# AcceLog_v00.net
KiCad netlist of a schematic drawn in EAGLE
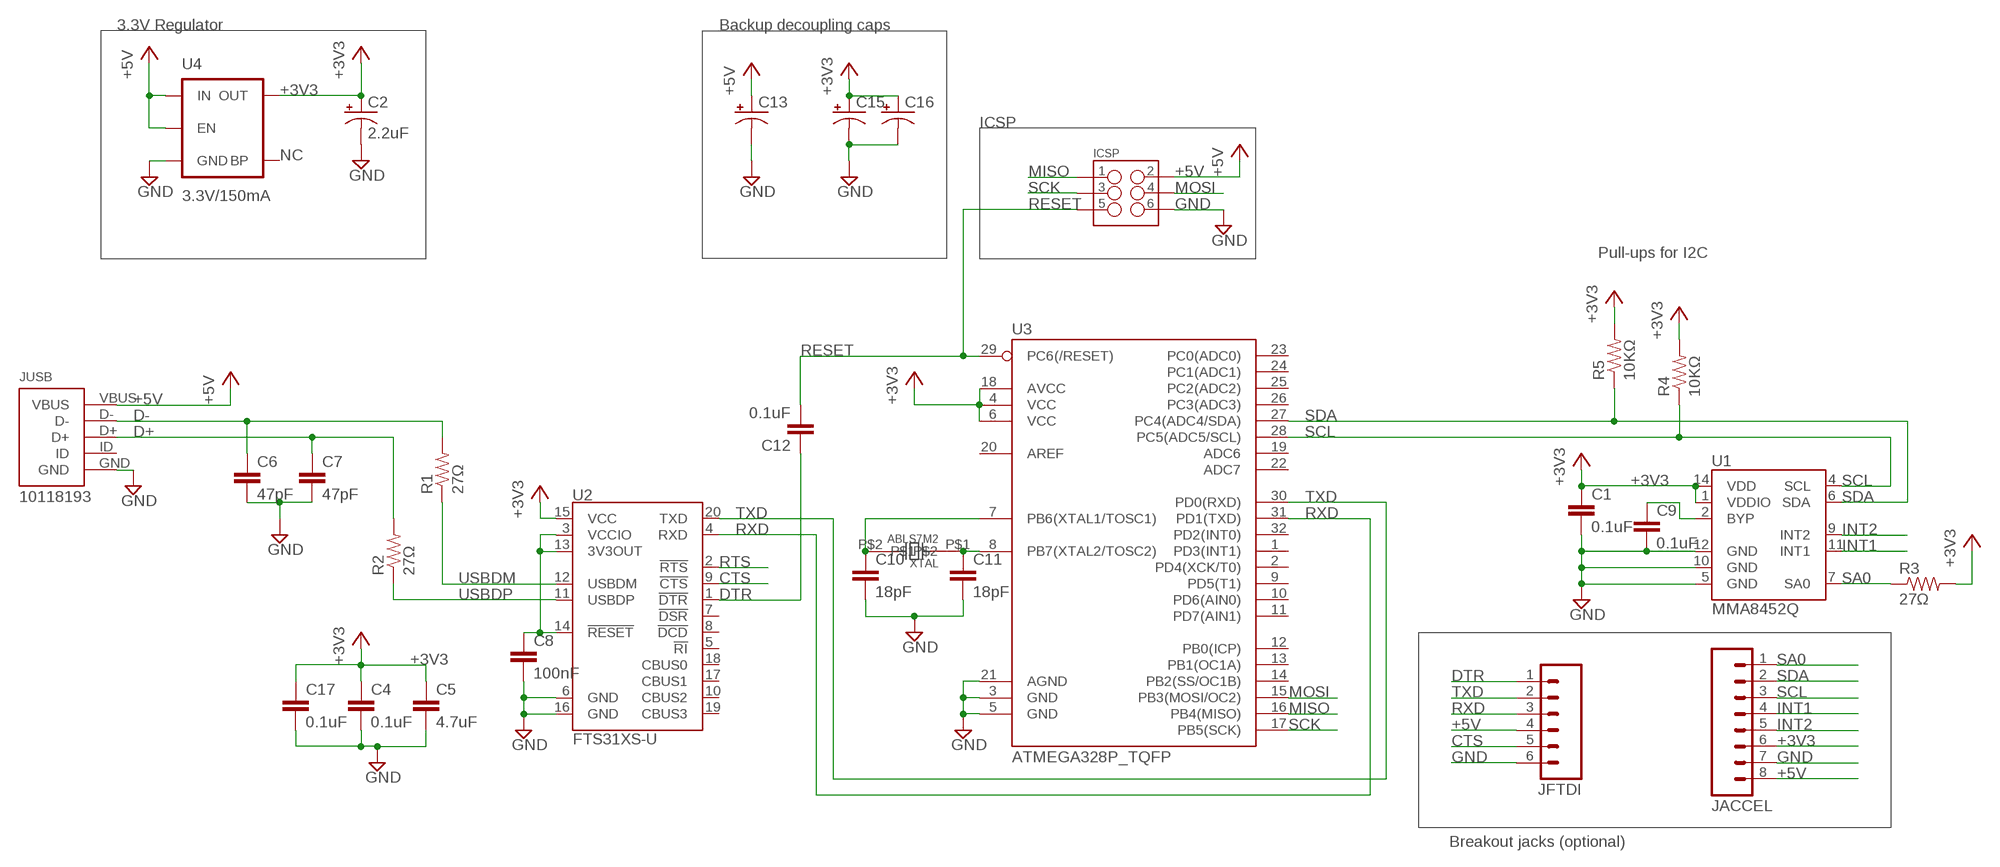
[diagram p0: schematic, sheet 1]

(export (version "E")
  (design (tool "Eeschema 10.0.6"))
  (components
    (comp (ref "C1")
      (value "0.1uF")
      (footprint "eagle-import:0603-CAP")
      (libsource (lib "eagle-import") (part "CAP0603-CAP"))
    )
    (comp (ref "C2")
      (value "2.2uF")
      (footprint "eagle-import:EIA3216")
      (libsource (lib "eagle-import") (part "CAP_POL1206"))
    )
    (comp (ref "C4")
      (value "0.1uF")
      (footprint "eagle-import:0603-CAP")
      (libsource (lib "eagle-import") (part "CAP0603-CAP"))
    )
    (comp (ref "C5")
      (value "4.7uF")
      (footprint "eagle-import:0603-CAP")
      (libsource (lib "eagle-import") (part "CAP0603-CAP"))
    )
    (comp (ref "C6")
      (value "47pF")
      (footprint "eagle-import:0603-CAP")
      (libsource (lib "eagle-import") (part "CAP0603-CAP"))
    )
    (comp (ref "C7")
      (value "47pF")
      (footprint "eagle-import:0603-CAP")
      (libsource (lib "eagle-import") (part "CAP0603-CAP"))
    )
    (comp (ref "C8")
      (value "100nF")
      (footprint "eagle-import:0603-CAP")
      (libsource (lib "eagle-import") (part "CAP0603-CAP"))
    )
    (comp (ref "C9")
      (value "0.1uF")
      (footprint "eagle-import:0603-CAP")
      (libsource (lib "eagle-import") (part "CAP0603-CAP"))
    )
    (comp (ref "C10")
      (value "18pF")
      (footprint "eagle-import:0603-CAP")
      (libsource (lib "eagle-import") (part "CAP0603-CAP"))
    )
    (comp (ref "C11")
      (value "18pF")
      (footprint "eagle-import:0603-CAP")
      (libsource (lib "eagle-import") (part "CAP0603-CAP"))
    )
    (comp (ref "C12")
      (value "0.1uF")
      (footprint "eagle-import:0603-CAP")
      (libsource (lib "eagle-import") (part "CAP0603-CAP"))
    )
    (comp (ref "C13")
      (value "CPOL-USE2-5")
      (footprint "eagle-import:E2-5")
      (libsource (lib "eagle-import") (part "CPOL-USE2-5"))
    )
    (comp (ref "C15")
      (value "CPOL-USE2-5")
      (footprint "eagle-import:E2-5")
      (libsource (lib "eagle-import") (part "CPOL-USE2-5"))
    )
    (comp (ref "C16")
      (value "CPOL-USE2-5")
      (footprint "eagle-import:E2-5")
      (libsource (lib "eagle-import") (part "CPOL-USE2-5"))
    )
    (comp (ref "C17")
      (value "0.1uF")
      (footprint "eagle-import:0603-CAP")
      (libsource (lib "eagle-import") (part "CAP0603-CAP"))
    )
    (comp (ref "ICSP")
      (value "M03X22X3_SILK_MALE_PTH")
      (footprint "eagle-import:2X3")
      (libsource (lib "eagle-import") (part "M03X22X3_SILK_MALE_PTH"))
    )
    (comp (ref "JACCEL")
      (value "M08LOCK")
      (footprint "eagle-import:1X08_LOCK")
      (libsource (lib "eagle-import") (part "M08LOCK"))
    )
    (comp (ref "JFTDI")
      (value "M06LOCK")
      (footprint "eagle-import:1X06_LOCK")
      (libsource (lib "eagle-import") (part "M06LOCK"))
    )
    (comp (ref "JUSB")
      (value "10118193")
      (footprint "eagle-import:10118193")
      (libsource (lib "eagle-import") (part "10118193"))
    )
    (comp (ref "R1")
      (value "27Ω")
      (footprint "eagle-import:0603-RES")
      (libsource (lib "eagle-import") (part "RESISTOR0603-RES"))
    )
    (comp (ref "R2")
      (value "27Ω")
      (footprint "eagle-import:0603-RES")
      (libsource (lib "eagle-import") (part "RESISTOR0603-RES"))
    )
    (comp (ref "R3")
      (value "27Ω")
      (footprint "eagle-import:0603-RES")
      (libsource (lib "eagle-import") (part "RESISTOR0603-RES"))
    )
    (comp (ref "R4")
      (value "10KΩ")
      (footprint "eagle-import:0603-RES")
      (libsource (lib "eagle-import") (part "RESISTOR0603-RES"))
    )
    (comp (ref "R5")
      (value "10KΩ")
      (footprint "eagle-import:0603-RES")
      (libsource (lib "eagle-import") (part "RESISTOR0603-RES"))
    )
    (comp (ref "U1")
      (value "MMA8452Q")
      (footprint "eagle-import:QFN-16_0.5MM")
      (libsource (lib "eagle-import") (part "MMA8452Q"))
    )
    (comp (ref "U2")
      (value "FTS31XS-U")
      (footprint "eagle-import:SSOP20_L")
      (libsource (lib "eagle-import") (part "FT231XS"))
    )
    (comp (ref "U3")
      (value "ATMEGA328P_TQFP")
      (footprint "eagle-import:TQFP32-08")
      (libsource (lib "eagle-import") (part "ATMEGA328P_TQFP"))
    )
    (comp (ref "U4")
      (value "3.3V/150mA")
      (footprint "eagle-import:SOT23-5")
      (libsource (lib "eagle-import") (part "V_REG_MIC52053.3V"))
    )
    (comp (ref "XTAL")
      (value "ABLS7M2")
      (footprint "eagle-import:ABLS7M2")
      (libsource (lib "eagle-import") (part "ABLS7M2"))
    )
  )
  (nets
    (net (code "1") (name "+3V3") (class "Default")
      (node (ref "C1") (pin "1") (pinfunction "1_1") (pintype "passive"))
      (node (ref "C15") (pin "+") (pinfunction "+_+") (pintype "passive"))
      (node (ref "C16") (pin "+") (pinfunction "+_+") (pintype "passive"))
      (node (ref "C17") (pin "1") (pinfunction "1_1") (pintype "passive"))
      (node (ref "C2") (pin "A") (pinfunction "+_A") (pintype "passive"))
      (node (ref "C4") (pin "1") (pinfunction "1_1") (pintype "passive"))
      (node (ref "C5") (pin "1") (pinfunction "1_1") (pintype "passive"))
      (node (ref "JACCEL") (pin "6") (pinfunction "6_6") (pintype "passive"))
      (node (ref "R3") (pin "2") (pinfunction "2_2") (pintype "passive"))
      (node (ref "R4") (pin "2") (pinfunction "2_2") (pintype "passive"))
      (node (ref "R5") (pin "2") (pinfunction "2_2") (pintype "passive"))
      (node (ref "U1") (pin "1") (pinfunction "VDDIO_1") (pintype "bidirectional"))
      (node (ref "U1") (pin "14") (pinfunction "VDD_14") (pintype "bidirectional"))
      (node (ref "U2") (pin "15") (pinfunction "VCC_15") (pintype "bidirectional"))
      (node (ref "U3") (pin "18") (pinfunction "AVCC_18") (pintype "bidirectional"))
      (node (ref "U3") (pin "4") (pinfunction "VCC_4") (pintype "bidirectional"))
      (node (ref "U3") (pin "6") (pinfunction "VCC_6") (pintype "bidirectional"))
      (node (ref "U4") (pin "5") (pinfunction "OUT_5") (pintype "passive"))
    )
    (net (code "2") (name "+5V") (class "Default")
      (node (ref "C13") (pin "+") (pinfunction "+_+") (pintype "passive"))
      (node (ref "ICSP") (pin "2") (pinfunction "2_2") (pintype "bidirectional"))
      (node (ref "JACCEL") (pin "8") (pinfunction "8_8") (pintype "passive"))
      (node (ref "JFTDI") (pin "4") (pinfunction "4_4") (pintype "passive"))
      (node (ref "JUSB") (pin "VBUS") (pinfunction "VBUS_VBUS") (pintype "bidirectional"))
      (node (ref "U4") (pin "1") (pinfunction "IN_1") (pintype "input"))
      (node (ref "U4") (pin "3") (pinfunction "EN_3") (pintype "input"))
    )
    (net (code "3") (name "/CTS") (class "Default")
      (node (ref "JFTDI") (pin "5") (pinfunction "5_5") (pintype "passive"))
      (node (ref "U2") (pin "9") (pinfunction "~{CTS}_9") (pintype "bidirectional"))
    )
    (net (code "4") (name "/D+") (class "Default")
      (node (ref "C7") (pin "1") (pinfunction "1_1") (pintype "passive"))
      (node (ref "JUSB") (pin "D+") (pinfunction "D+_D+") (pintype "bidirectional"))
      (node (ref "R2") (pin "2") (pinfunction "2_2") (pintype "passive"))
    )
    (net (code "5") (name "/D-") (class "Default")
      (node (ref "C6") (pin "1") (pinfunction "1_1") (pintype "passive"))
      (node (ref "JUSB") (pin "D-") (pinfunction "D-_D-") (pintype "bidirectional"))
      (node (ref "R1") (pin "2") (pinfunction "2_2") (pintype "passive"))
    )
    (net (code "6") (name "/DTR") (class "Default")
      (node (ref "C12") (pin "1") (pinfunction "1_1") (pintype "passive"))
      (node (ref "JFTDI") (pin "1") (pinfunction "1_1") (pintype "passive"))
      (node (ref "U2") (pin "1") (pinfunction "~{DTR}_1") (pintype "bidirectional"))
    )
    (net (code "7") (name "/INT1") (class "Default")
      (node (ref "JACCEL") (pin "4") (pinfunction "4_4") (pintype "passive"))
      (node (ref "U1") (pin "11") (pinfunction "INT1_11") (pintype "bidirectional"))
    )
    (net (code "8") (name "/INT2") (class "Default")
      (node (ref "JACCEL") (pin "5") (pinfunction "5_5") (pintype "passive"))
      (node (ref "U1") (pin "9") (pinfunction "INT2_9") (pintype "bidirectional"))
    )
    (net (code "9") (name "/MISO") (class "Default")
      (node (ref "ICSP") (pin "1") (pinfunction "1_1") (pintype "bidirectional"))
      (node (ref "U3") (pin "16") (pinfunction "PB4(MISO)_16") (pintype "bidirectional"))
    )
    (net (code "10") (name "/MOSI") (class "Default")
      (node (ref "ICSP") (pin "4") (pinfunction "4_4") (pintype "bidirectional"))
      (node (ref "U3") (pin "15") (pinfunction "PB3(MOSI/OC2)_15") (pintype "bidirectional"))
    )
    (net (code "11") (name "/RESET") (class "Default")
      (node (ref "C12") (pin "2") (pinfunction "2_2") (pintype "passive"))
      (node (ref "ICSP") (pin "5") (pinfunction "5_5") (pintype "bidirectional"))
      (node (ref "U3") (pin "29") (pinfunction "PC6(/RESET)_29") (pintype "bidirectional"))
    )
    (net (code "12") (name "/RTS") (class "Default")
      (node (ref "U2") (pin "2") (pinfunction "~{RTS}_2") (pintype "bidirectional"))
    )
    (net (code "13") (name "/RXD") (class "Default")
      (node (ref "JFTDI") (pin "3") (pinfunction "3_3") (pintype "passive"))
      (node (ref "U2") (pin "4") (pinfunction "RXD_4") (pintype "bidirectional"))
      (node (ref "U3") (pin "31") (pinfunction "PD1(TXD)_31") (pintype "bidirectional"))
    )
    (net (code "14") (name "/SA0") (class "Default")
      (node (ref "JACCEL") (pin "1") (pinfunction "1_1") (pintype "passive"))
      (node (ref "R3") (pin "1") (pinfunction "1_1") (pintype "passive"))
      (node (ref "U1") (pin "7") (pinfunction "SA0_7") (pintype "bidirectional"))
    )
    (net (code "15") (name "/SCK") (class "Default")
      (node (ref "ICSP") (pin "3") (pinfunction "3_3") (pintype "bidirectional"))
      (node (ref "U3") (pin "17") (pinfunction "PB5(SCK)_17") (pintype "bidirectional"))
    )
    (net (code "16") (name "/SCL") (class "Default")
      (node (ref "JACCEL") (pin "3") (pinfunction "3_3") (pintype "passive"))
      (node (ref "R4") (pin "1") (pinfunction "1_1") (pintype "passive"))
      (node (ref "U1") (pin "4") (pinfunction "SCL_4") (pintype "bidirectional"))
      (node (ref "U3") (pin "28") (pinfunction "PC5(ADC5/SCL)_28") (pintype "bidirectional"))
    )
    (net (code "17") (name "/SDA") (class "Default")
      (node (ref "JACCEL") (pin "2") (pinfunction "2_2") (pintype "passive"))
      (node (ref "R5") (pin "1") (pinfunction "1_1") (pintype "passive"))
      (node (ref "U1") (pin "6") (pinfunction "SDA_6") (pintype "bidirectional"))
      (node (ref "U3") (pin "27") (pinfunction "PC4(ADC4/SDA)_27") (pintype "bidirectional"))
    )
    (net (code "18") (name "/TXD") (class "Default")
      (node (ref "JFTDI") (pin "2") (pinfunction "2_2") (pintype "passive"))
      (node (ref "U2") (pin "20") (pinfunction "TXD_20") (pintype "bidirectional"))
      (node (ref "U3") (pin "30") (pinfunction "PD0(RXD)_30") (pintype "bidirectional"))
    )
    (net (code "19") (name "/USBDM") (class "Default")
      (node (ref "R1") (pin "1") (pinfunction "1_1") (pintype "passive"))
      (node (ref "U2") (pin "12") (pinfunction "USBDM_12") (pintype "bidirectional"))
    )
    (net (code "20") (name "/USBDP") (class "Default")
      (node (ref "R2") (pin "1") (pinfunction "1_1") (pintype "passive"))
      (node (ref "U2") (pin "11") (pinfunction "USBDP_11") (pintype "bidirectional"))
    )
    (net (code "21") (name "GND") (class "Default")
      (node (ref "C1") (pin "2") (pinfunction "2_2") (pintype "passive"))
      (node (ref "C10") (pin "2") (pinfunction "2_2") (pintype "passive"))
      (node (ref "C11") (pin "2") (pinfunction "2_2") (pintype "passive"))
      (node (ref "C13") (pin "-") (pinfunction "-_-") (pintype "passive"))
      (node (ref "C15") (pin "-") (pinfunction "-_-") (pintype "passive"))
      (node (ref "C16") (pin "-") (pinfunction "-_-") (pintype "passive"))
      (node (ref "C17") (pin "2") (pinfunction "2_2") (pintype "passive"))
      (node (ref "C2") (pin "C") (pinfunction "-_C") (pintype "passive"))
      (node (ref "C4") (pin "2") (pinfunction "2_2") (pintype "passive"))
      (node (ref "C5") (pin "2") (pinfunction "2_2") (pintype "passive"))
      (node (ref "C6") (pin "2") (pinfunction "2_2") (pintype "passive"))
      (node (ref "C7") (pin "2") (pinfunction "2_2") (pintype "passive"))
      (node (ref "C8") (pin "2") (pinfunction "2_2") (pintype "passive"))
      (node (ref "C9") (pin "2") (pinfunction "2_2") (pintype "passive"))
      (node (ref "ICSP") (pin "6") (pinfunction "6_6") (pintype "bidirectional"))
      (node (ref "JACCEL") (pin "7") (pinfunction "7_7") (pintype "passive"))
      (node (ref "JFTDI") (pin "6") (pinfunction "6_6") (pintype "passive"))
      (node (ref "JUSB") (pin "GND") (pinfunction "GND_GND") (pintype "bidirectional"))
      (node (ref "U1") (pin "10") (pinfunction "GND_10") (pintype "bidirectional"))
      (node (ref "U1") (pin "12") (pinfunction "GND_12") (pintype "bidirectional"))
      (node (ref "U1") (pin "5") (pinfunction "GND_5") (pintype "bidirectional"))
      (node (ref "U2") (pin "16") (pinfunction "GND_16") (pintype "bidirectional"))
      (node (ref "U2") (pin "6") (pinfunction "GND_6") (pintype "bidirectional"))
      (node (ref "U3") (pin "21") (pinfunction "AGND_21") (pintype "bidirectional"))
      (node (ref "U3") (pin "3") (pinfunction "GND_3") (pintype "bidirectional"))
      (node (ref "U3") (pin "5") (pinfunction "GND_5") (pintype "bidirectional"))
      (node (ref "U4") (pin "2") (pinfunction "GND_2") (pintype "input"))
    )
    (net (code "22") (name "Net-(U1-BYP)") (class "Default")
      (node (ref "C9") (pin "1") (pinfunction "1_1") (pintype "passive"))
      (node (ref "U1") (pin "2") (pinfunction "BYP_2") (pintype "bidirectional"))
    )
    (net (code "23") (name "Net-(U2-3V3OUT)") (class "Default")
      (node (ref "C8") (pin "1") (pinfunction "1_1") (pintype "passive"))
      (node (ref "U2") (pin "13") (pinfunction "3V3OUT_13") (pintype "bidirectional"))
      (node (ref "U2") (pin "14") (pinfunction "~{RESET}_14") (pintype "bidirectional"))
      (node (ref "U2") (pin "3") (pinfunction "VCCIO_3") (pintype "bidirectional"))
    )
    (net (code "24") (name "Net-(U3-PB6(XTAL1{slash}TOSC1))") (class "Default")
      (node (ref "C10") (pin "1") (pinfunction "1_1") (pintype "passive"))
      (node (ref "U3") (pin "7") (pinfunction "PB6(XTAL1/TOSC1)_7") (pintype "bidirectional"))
      (node (ref "XTAL") (pin "P$2") (pinfunction "P$2_P$2") (pintype "bidirectional"))
    )
    (net (code "25") (name "Net-(U3-PB7(XTAL2{slash}TOSC2))") (class "Default")
      (node (ref "C11") (pin "1") (pinfunction "1_1") (pintype "passive"))
      (node (ref "U3") (pin "8") (pinfunction "PB7(XTAL2/TOSC2)_8") (pintype "bidirectional"))
      (node (ref "XTAL") (pin "P$1") (pinfunction "P$1_P$1") (pintype "bidirectional"))
    )
    (net (code "26") (name "unconnected-(JUSB-PadID)") (class "Default")
      (node (ref "JUSB") (pin "ID") (pinfunction "ID_ID") (pintype "bidirectional"))
    )
    (net (code "27") (name "unconnected-(U2-CBUS0-Pad18)") (class "Default")
      (node (ref "U2") (pin "18") (pinfunction "CBUS0_18") (pintype "bidirectional"))
    )
    (net (code "28") (name "unconnected-(U2-CBUS1-Pad17)") (class "Default")
      (node (ref "U2") (pin "17") (pinfunction "CBUS1_17") (pintype "bidirectional"))
    )
    (net (code "29") (name "unconnected-(U2-CBUS2-Pad10)") (class "Default")
      (node (ref "U2") (pin "10") (pinfunction "CBUS2_10") (pintype "bidirectional"))
    )
    (net (code "30") (name "unconnected-(U2-CBUS3-Pad19)") (class "Default")
      (node (ref "U2") (pin "19") (pinfunction "CBUS3_19") (pintype "bidirectional"))
    )
    (net (code "31") (name "unconnected-(U2-~{DCD}-Pad8)") (class "Default")
      (node (ref "U2") (pin "8") (pinfunction "~{DCD}_8") (pintype "bidirectional"))
    )
    (net (code "32") (name "unconnected-(U2-~{DSR}-Pad7)") (class "Default")
      (node (ref "U2") (pin "7") (pinfunction "~{DSR}_7") (pintype "bidirectional"))
    )
    (net (code "33") (name "unconnected-(U2-~{RI}-Pad5)") (class "Default")
      (node (ref "U2") (pin "5") (pinfunction "~{RI}_5") (pintype "bidirectional"))
    )
    (net (code "34") (name "unconnected-(U3-ADC6-Pad19)") (class "Default")
      (node (ref "U3") (pin "19") (pinfunction "ADC6_19") (pintype "bidirectional"))
    )
    (net (code "35") (name "unconnected-(U3-ADC7-Pad22)") (class "Default")
      (node (ref "U3") (pin "22") (pinfunction "ADC7_22") (pintype "bidirectional"))
    )
    (net (code "36") (name "unconnected-(U3-AREF-Pad20)") (class "Default")
      (node (ref "U3") (pin "20") (pinfunction "AREF_20") (pintype "bidirectional"))
    )
    (net (code "37") (name "unconnected-(U3-PB0(ICP)-Pad12)") (class "Default")
      (node (ref "U3") (pin "12") (pinfunction "PB0(ICP)_12") (pintype "bidirectional"))
    )
    (net (code "38") (name "unconnected-(U3-PB1(OC1A)-Pad13)") (class "Default")
      (node (ref "U3") (pin "13") (pinfunction "PB1(OC1A)_13") (pintype "bidirectional"))
    )
    (net (code "39") (name "unconnected-(U3-PB2(SS{slash}OC1B)-Pad14)") (class "Default")
      (node (ref "U3") (pin "14") (pinfunction "PB2(SS/OC1B)_14") (pintype "bidirectional"))
    )
    (net (code "40") (name "unconnected-(U3-PC0(ADC0)-Pad23)") (class "Default")
      (node (ref "U3") (pin "23") (pinfunction "PC0(ADC0)_23") (pintype "bidirectional"))
    )
    (net (code "41") (name "unconnected-(U3-PC1(ADC1)-Pad24)") (class "Default")
      (node (ref "U3") (pin "24") (pinfunction "PC1(ADC1)_24") (pintype "bidirectional"))
    )
    (net (code "42") (name "unconnected-(U3-PC2(ADC2)-Pad25)") (class "Default")
      (node (ref "U3") (pin "25") (pinfunction "PC2(ADC2)_25") (pintype "bidirectional"))
    )
    (net (code "43") (name "unconnected-(U3-PC3(ADC3)-Pad26)") (class "Default")
      (node (ref "U3") (pin "26") (pinfunction "PC3(ADC3)_26") (pintype "bidirectional"))
    )
    (net (code "44") (name "unconnected-(U3-PD2(INT0)-Pad32)") (class "Default")
      (node (ref "U3") (pin "32") (pinfunction "PD2(INT0)_32") (pintype "bidirectional"))
    )
    (net (code "45") (name "unconnected-(U3-PD3(INT1)-Pad1)") (class "Default")
      (node (ref "U3") (pin "1") (pinfunction "PD3(INT1)_1") (pintype "bidirectional"))
    )
    (net (code "46") (name "unconnected-(U3-PD4(XCK{slash}T0)-Pad2)") (class "Default")
      (node (ref "U3") (pin "2") (pinfunction "PD4(XCK/T0)_2") (pintype "bidirectional"))
    )
    (net (code "47") (name "unconnected-(U3-PD5(T1)-Pad9)") (class "Default")
      (node (ref "U3") (pin "9") (pinfunction "PD5(T1)_9") (pintype "bidirectional"))
    )
    (net (code "48") (name "unconnected-(U3-PD6(AIN0)-Pad10)") (class "Default")
      (node (ref "U3") (pin "10") (pinfunction "PD6(AIN0)_10") (pintype "bidirectional"))
    )
    (net (code "49") (name "unconnected-(U3-PD7(AIN1)-Pad11)") (class "Default")
      (node (ref "U3") (pin "11") (pinfunction "PD7(AIN1)_11") (pintype "bidirectional"))
    )
    (net (code "50") (name "unconnected-(U4-BP-Pad4)") (class "Default")
      (node (ref "U4") (pin "4") (pinfunction "BP_4") (pintype "input"))
    )
  )
)
